# audio.net
KiCad netlist of a schematic drawn in Altium Designer
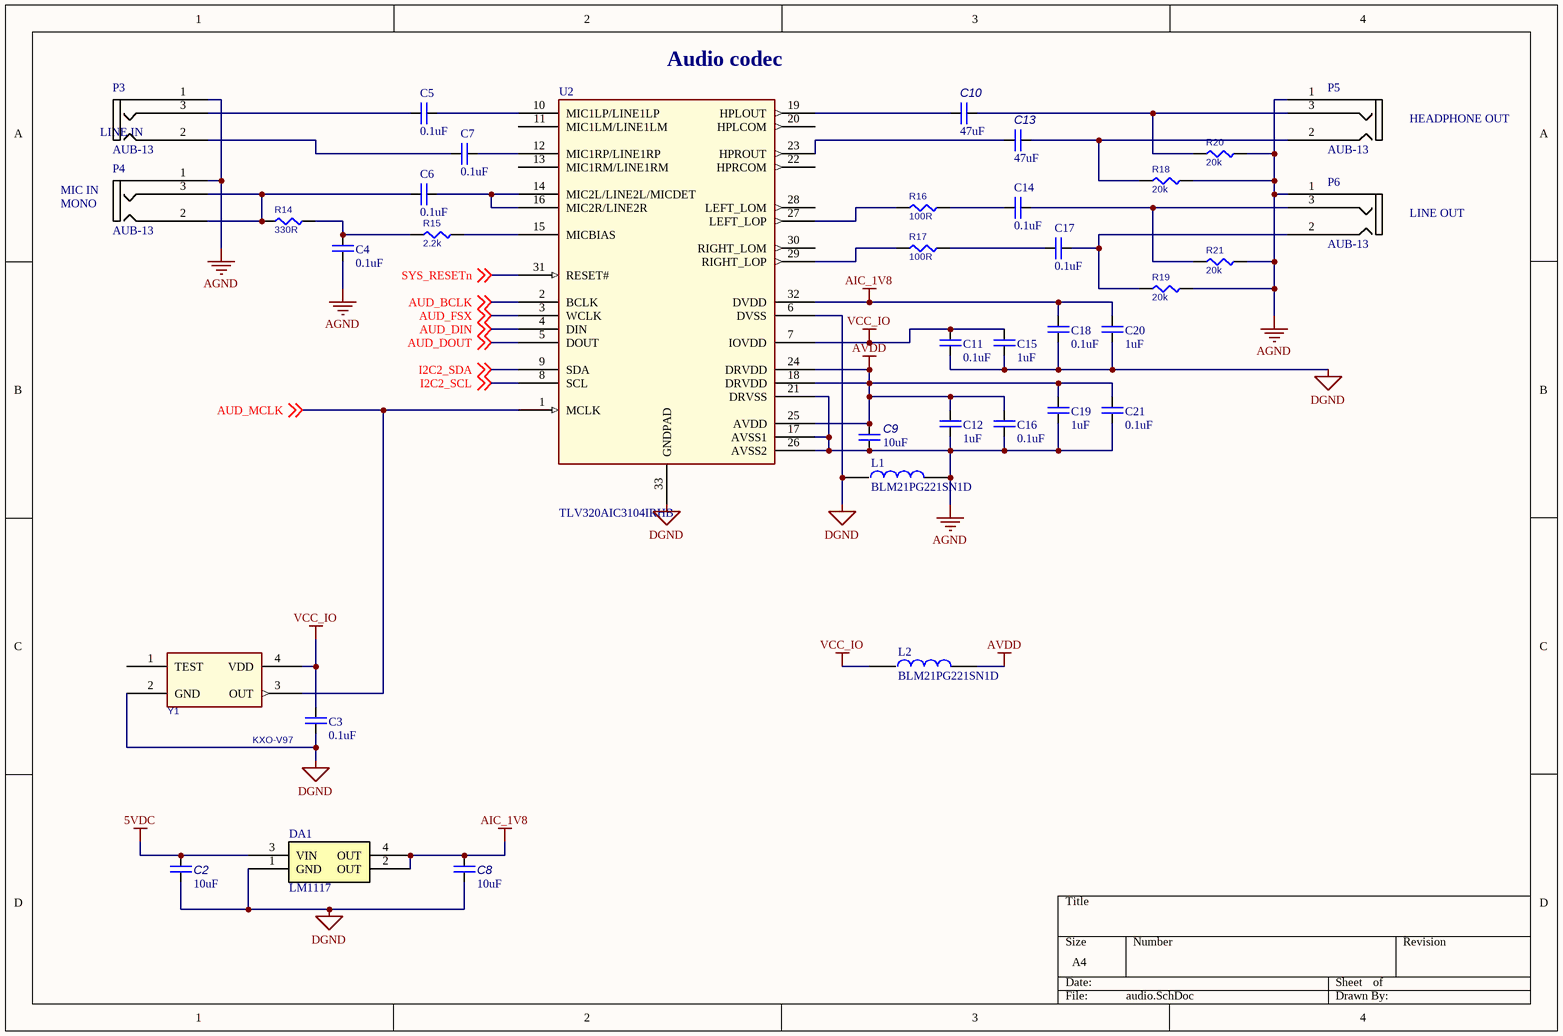
[diagram p0: audio.SchDoc]

(export (version "E")
  (design (tool "Eeschema 10.0.6"))
  (components
    (comp (ref "C2")
      (value "10uF")
      (footprint "CC2012-0805")
      (description "C0805")
      (libsource (lib "usomiq-audio") (part "C0805"))
    )
    (comp (ref "C3")
      (value "0.1uF")
      (footprint "CHIP0603")
      (description "Ceramic capacitor C0603")
      (fields (field (name "Comment") "C0603"))
      (libsource (lib "usomiq-audio") (part "C0603"))
    )
    (comp (ref "C4")
      (value "0.1uF")
      (footprint "CHIP0603")
      (description "Ceramic capacitor C0603")
      (fields (field (name "Comment") "C0603"))
      (libsource (lib "usomiq-audio") (part "C0603"))
    )
    (comp (ref "C5")
      (value "0.1uF")
      (footprint "CHIP0603")
      (description "Ceramic capacitor C0603")
      (fields (field (name "Comment") "C0603"))
      (libsource (lib "usomiq-audio") (part "C0603"))
    )
    (comp (ref "C6")
      (value "0.1uF")
      (footprint "CHIP0603")
      (description "Ceramic capacitor C0603")
      (fields (field (name "Comment") "C0603"))
      (libsource (lib "usomiq-audio") (part "C0603"))
    )
    (comp (ref "C7")
      (value "0.1uF")
      (footprint "CHIP0603")
      (description "Ceramic capacitor C0603")
      (fields (field (name "Comment") "C0603"))
      (libsource (lib "usomiq-audio") (part "C0603"))
    )
    (comp (ref "C8")
      (value "10uF")
      (footprint "CC2012-0805")
      (description "C0805")
      (libsource (lib "usomiq-audio") (part "C0805"))
    )
    (comp (ref "C9")
      (value "10uF")
      (footprint "CC2012-0805")
      (description "C0805")
      (libsource (lib "usomiq-audio") (part "C0805"))
    )
    (comp (ref "C10")
      (value "47uF")
      (footprint "CC3216-1206")
      (description "C1206")
      (libsource (lib "usomiq-audio") (part "C1206"))
    )
    (comp (ref "C11")
      (value "0.1uF")
      (footprint "CHIP0603")
      (description "Ceramic capacitor C0603")
      (fields (field (name "Comment") "C0603"))
      (libsource (lib "usomiq-audio") (part "C0603"))
    )
    (comp (ref "C12")
      (value "1uF")
      (footprint "CHIP0603")
      (description "Ceramic capacitor C0603")
      (fields (field (name "Comment") "C0603"))
      (libsource (lib "usomiq-audio") (part "C0603"))
    )
    (comp (ref "C13")
      (value "47uF")
      (footprint "CC3216-1206")
      (description "C1206")
      (libsource (lib "usomiq-audio") (part "C1206"))
    )
    (comp (ref "C14")
      (value "0.1uF")
      (footprint "CHIP0603")
      (description "Ceramic capacitor C0603")
      (fields (field (name "Comment") "C0603"))
      (libsource (lib "usomiq-audio") (part "C0603"))
    )
    (comp (ref "C15")
      (value "1uF")
      (footprint "CHIP0603")
      (description "Ceramic capacitor C0603")
      (fields (field (name "Comment") "C0603"))
      (libsource (lib "usomiq-audio") (part "C0603"))
    )
    (comp (ref "C16")
      (value "0.1uF")
      (footprint "CHIP0603")
      (description "Ceramic capacitor C0603")
      (fields (field (name "Comment") "C0603"))
      (libsource (lib "usomiq-audio") (part "C0603"))
    )
    (comp (ref "C17")
      (value "0.1uF")
      (footprint "CHIP0603")
      (description "Ceramic capacitor C0603")
      (fields (field (name "Comment") "C0603"))
      (libsource (lib "usomiq-audio") (part "C0603"))
    )
    (comp (ref "C18")
      (value "0.1uF")
      (footprint "CHIP0603")
      (description "Ceramic capacitor C0603")
      (fields (field (name "Comment") "C0603"))
      (libsource (lib "usomiq-audio") (part "C0603"))
    )
    (comp (ref "C19")
      (value "1uF")
      (footprint "CHIP0603")
      (description "Ceramic capacitor C0603")
      (fields (field (name "Comment") "C0603"))
      (libsource (lib "usomiq-audio") (part "C0603"))
    )
    (comp (ref "C20")
      (value "1uF")
      (footprint "CHIP0603")
      (description "Ceramic capacitor C0603")
      (fields (field (name "Comment") "C0603"))
      (libsource (lib "usomiq-audio") (part "C0603"))
    )
    (comp (ref "C21")
      (value "0.1uF")
      (footprint "CHIP0603")
      (description "Ceramic capacitor C0603")
      (fields (field (name "Comment") "C0603"))
      (libsource (lib "usomiq-audio") (part "C0603"))
    )
    (comp (ref "DA1")
      (value "LM1117")
      (footprint "SOT230P700X160-4N")
      (description "800mA Low-Dropout Linear Regulator")
      (fields (field (name "MANUFACTURER") "National"))
      (libsource (lib "usomiq-audio") (part "LM1117"))
    )
    (comp (ref "L1")
      (value "BLM21PG221SN1D")
      (footprint "Chip2PinSM127P600-8N")
      (fields (field (name "MANUFACTURER") "Murata"))
      (libsource (lib "usomiq-audio") (part "BLM21PG221SN1D"))
    )
    (comp (ref "L2")
      (value "BLM21PG221SN1D")
      (footprint "Chip2PinSM127P600-8N")
      (fields (field (name "MANUFACTURER") "Murata"))
      (libsource (lib "usomiq-audio") (part "BLM21PG221SN1D"))
    )
    (comp (ref "P3")
      (value "AUB-13")
      (footprint "AUB_13")
      (description "Audio connector mini-jack 3.5mm, 3 pins")
      (libsource (lib "usomiq-audio") (part "AUB-13"))
    )
    (comp (ref "P4")
      (value "AUB-13")
      (footprint "AUB_13")
      (description "Audio connector mini-jack 3.5mm, 3 pins")
      (libsource (lib "usomiq-audio") (part "AUB-13"))
    )
    (comp (ref "P5")
      (value "AUB-13")
      (footprint "AUB_13")
      (description "Audio connector mini-jack 3.5mm, 3 pins")
      (libsource (lib "usomiq-audio") (part "AUB-13"))
    )
    (comp (ref "P6")
      (value "AUB-13")
      (footprint "AUB_13")
      (description "Audio connector mini-jack 3.5mm, 3 pins")
      (libsource (lib "usomiq-audio") (part "AUB-13"))
    )
    (comp (ref "R14")
      (value "330R")
      (footprint "CHIP0603")
      (description "Resistor 0603")
      (fields (field (name "Comment") "R0603"))
      (libsource (lib "usomiq-audio") (part "R0603"))
    )
    (comp (ref "R15")
      (value "2.2k")
      (footprint "CHIP0603")
      (description "Resistor 0603")
      (fields (field (name "Comment") "R0603"))
      (libsource (lib "usomiq-audio") (part "R0603"))
    )
    (comp (ref "R16")
      (value "100R")
      (footprint "CHIP0603")
      (description "Resistor 0603")
      (fields (field (name "Comment") "R0603"))
      (libsource (lib "usomiq-audio") (part "R0603"))
    )
    (comp (ref "R17")
      (value "100R")
      (footprint "CHIP0603")
      (description "Resistor 0603")
      (fields (field (name "Comment") "R0603"))
      (libsource (lib "usomiq-audio") (part "R0603"))
    )
    (comp (ref "R18")
      (value "20k")
      (footprint "CHIP0603")
      (description "Resistor 0603")
      (fields (field (name "Comment") "R0603"))
      (libsource (lib "usomiq-audio") (part "R0603"))
    )
    (comp (ref "R19")
      (value "20k")
      (footprint "CHIP0603")
      (description "Resistor 0603")
      (fields (field (name "Comment") "R0603"))
      (libsource (lib "usomiq-audio") (part "R0603"))
    )
    (comp (ref "R20")
      (value "20k")
      (footprint "CHIP0603")
      (description "Resistor 0603")
      (fields (field (name "Comment") "R0603"))
      (libsource (lib "usomiq-audio") (part "R0603"))
    )
    (comp (ref "R21")
      (value "20k")
      (footprint "CHIP0603")
      (description "Resistor 0603")
      (fields (field (name "Comment") "R0603"))
      (libsource (lib "usomiq-audio") (part "R0603"))
    )
    (comp (ref "U2")
      (value "TLV320AIC3104")
      (footprint "QFN32")
      (description "LOW-POWER STEREO AUDIO CODEC FOR PORTABLE AUDIO/TELEPHONY")
      (fields (field (name "MANUFACTURER") "TI") (field (name "MAN P/N") "TLV320AIC3104IRHB"))
      (libsource (lib "usomiq-audio") (part "TLV320AIC3104"))
    )
    (comp (ref "Y1")
      (value "KXO-V97")
      (footprint "KXO_V97")
      (description "Quartz oscillator 7x5mm")
      (fields (field (name "MANUFACTURER") "Geyer"))
      (libsource (lib "usomiq-audio") (part "KXO-V97"))
    )
  )
  (nets
    (net (code "1") (name "5VDC") (class "Default")
      (node (ref "C2") (pin "2") (pinfunction "2_2") (pintype "passive"))
      (node (ref "DA1") (pin "3") (pinfunction "VIN_3") (pintype "power_in"))
    )
    (net (code "2") (name "AGND") (class "Default")
      (node (ref "C12") (pin "2") (pinfunction "2_2") (pintype "passive"))
      (node (ref "C16") (pin "2") (pinfunction "2_2") (pintype "passive"))
      (node (ref "C19") (pin "2") (pinfunction "2_2") (pintype "passive"))
      (node (ref "C21") (pin "2") (pinfunction "2_2") (pintype "passive"))
      (node (ref "C4") (pin "1") (pinfunction "1_1") (pintype "passive"))
      (node (ref "C9") (pin "1") (pinfunction "1_1") (pintype "passive"))
      (node (ref "L1") (pin "2") (pinfunction "2_2") (pintype "passive"))
      (node (ref "P3") (pin "1") (pinfunction "GND_1") (pintype "passive"))
      (node (ref "P4") (pin "1") (pinfunction "GND_1") (pintype "passive"))
      (node (ref "P5") (pin "1") (pinfunction "GND_1") (pintype "passive"))
      (node (ref "P6") (pin "1") (pinfunction "GND_1") (pintype "passive"))
      (node (ref "R18") (pin "1") (pinfunction "1_1") (pintype "passive"))
      (node (ref "R19") (pin "1") (pinfunction "1_1") (pintype "passive"))
      (node (ref "R20") (pin "1") (pinfunction "1_1") (pintype "passive"))
      (node (ref "R21") (pin "1") (pinfunction "1_1") (pintype "passive"))
      (node (ref "U2") (pin "17") (pinfunction "AVSS1_17") (pintype "power_in"))
      (node (ref "U2") (pin "21") (pinfunction "DRVSS_21") (pintype "power_in"))
      (node (ref "U2") (pin "26") (pinfunction "AVSS2_26") (pintype "power_in"))
    )
    (net (code "3") (name "AIC_1V8") (class "Default")
      (node (ref "C18") (pin "1") (pinfunction "1_1") (pintype "passive"))
      (node (ref "C20") (pin "1") (pinfunction "1_1") (pintype "passive"))
      (node (ref "C8") (pin "2") (pinfunction "2_2") (pintype "passive"))
      (node (ref "DA1") (pin "2") (pinfunction "OUT_2") (pintype "power_in"))
      (node (ref "DA1") (pin "4") (pinfunction "OUT_4") (pintype "power_in"))
      (node (ref "U2") (pin "32") (pinfunction "DVDD_32") (pintype "power_in"))
    )
    (net (code "4") (name "AUD_BCLK") (class "Default")
      (node (ref "U2") (pin "2") (pinfunction "BCLK_2") (pintype "passive"))
    )
    (net (code "5") (name "AUD_DIN") (class "Default")
      (node (ref "U2") (pin "4") (pinfunction "DIN_4") (pintype "passive"))
    )
    (net (code "6") (name "AUD_DOUT") (class "Default")
      (node (ref "U2") (pin "5") (pinfunction "DOUT_5") (pintype "passive"))
    )
    (net (code "7") (name "AUD_FSX") (class "Default")
      (node (ref "U2") (pin "3") (pinfunction "WCLK_3") (pintype "passive"))
    )
    (net (code "8") (name "AUD_MCLK") (class "Default")
      (node (ref "U2") (pin "1") (pinfunction "MCLK_1") (pintype "input"))
      (node (ref "Y1") (pin "3") (pinfunction "OUT_3") (pintype "output"))
    )
    (net (code "9") (name "AVDD") (class "Default")
      (node (ref "C12") (pin "1") (pinfunction "1_1") (pintype "passive"))
      (node (ref "C16") (pin "1") (pinfunction "1_1") (pintype "passive"))
      (node (ref "C19") (pin "1") (pinfunction "1_1") (pintype "passive"))
      (node (ref "C21") (pin "1") (pinfunction "1_1") (pintype "passive"))
      (node (ref "C9") (pin "2") (pinfunction "2_2") (pintype "passive"))
      (node (ref "L2") (pin "2") (pinfunction "2_2") (pintype "passive"))
      (node (ref "U2") (pin "18") (pinfunction "DRVDD_18") (pintype "power_in"))
      (node (ref "U2") (pin "24") (pinfunction "DRVDD_24") (pintype "power_in"))
      (node (ref "U2") (pin "25") (pinfunction "AVDD_25") (pintype "power_in"))
    )
    (net (code "10") (name "DGND") (class "Default")
      (node (ref "C11") (pin "2") (pinfunction "2_2") (pintype "passive"))
      (node (ref "C15") (pin "2") (pinfunction "2_2") (pintype "passive"))
      (node (ref "C18") (pin "2") (pinfunction "2_2") (pintype "passive"))
      (node (ref "C2") (pin "1") (pinfunction "1_1") (pintype "passive"))
      (node (ref "C20") (pin "2") (pinfunction "2_2") (pintype "passive"))
      (node (ref "C3") (pin "2") (pinfunction "2_2") (pintype "passive"))
      (node (ref "C8") (pin "1") (pinfunction "1_1") (pintype "passive"))
      (node (ref "DA1") (pin "1") (pinfunction "GND_1") (pintype "power_in"))
      (node (ref "L1") (pin "1") (pinfunction "1_1") (pintype "passive"))
      (node (ref "U2") (pin "33") (pinfunction "GNDPAD_33") (pintype "power_in"))
      (node (ref "U2") (pin "6") (pinfunction "DVSS_6") (pintype "power_in"))
      (node (ref "Y1") (pin "2") (pinfunction "GND_2") (pintype "power_in"))
    )
    (net (code "11") (name "I2C2_SCL") (class "Default")
      (node (ref "U2") (pin "8") (pinfunction "SCL_8") (pintype "passive"))
    )
    (net (code "12") (name "I2C2_SDA") (class "Default")
      (node (ref "U2") (pin "9") (pinfunction "SDA_9") (pintype "passive"))
    )
    (net (code "13") (name "Net-(C4-Pad2)") (class "Default")
      (node (ref "C4") (pin "2") (pinfunction "2_2") (pintype "passive"))
      (node (ref "R14") (pin "2") (pinfunction "2_2") (pintype "passive"))
      (node (ref "R15") (pin "1") (pinfunction "1_1") (pintype "passive"))
    )
    (net (code "14") (name "Net-(C14-Pad1)") (class "Default")
      (node (ref "C14") (pin "1") (pinfunction "1_1") (pintype "passive"))
      (node (ref "R16") (pin "2") (pinfunction "2_2") (pintype "passive"))
    )
    (net (code "15") (name "Net-(C17-Pad1)") (class "Default")
      (node (ref "C17") (pin "1") (pinfunction "1_1") (pintype "passive"))
      (node (ref "R17") (pin "2") (pinfunction "2_2") (pintype "passive"))
    )
    (net (code "16") (name "Net-(P3-LEFT)") (class "Default")
      (node (ref "C5") (pin "1") (pinfunction "1_1") (pintype "passive"))
      (node (ref "P3") (pin "3") (pinfunction "LEFT_3") (pintype "passive"))
    )
    (net (code "17") (name "Net-(P3-RIGHT)") (class "Default")
      (node (ref "C7") (pin "1") (pinfunction "1_1") (pintype "passive"))
      (node (ref "P3") (pin "2") (pinfunction "RIGHT_2") (pintype "passive"))
    )
    (net (code "18") (name "Net-(P4-LEFT)") (class "Default")
      (node (ref "C6") (pin "1") (pinfunction "1_1") (pintype "passive"))
      (node (ref "P4") (pin "2") (pinfunction "RIGHT_2") (pintype "passive"))
      (node (ref "P4") (pin "3") (pinfunction "LEFT_3") (pintype "passive"))
      (node (ref "R14") (pin "1") (pinfunction "1_1") (pintype "passive"))
    )
    (net (code "19") (name "Net-(P5-LEFT)") (class "Default")
      (node (ref "C10") (pin "1") (pinfunction "1_1") (pintype "passive"))
      (node (ref "P5") (pin "3") (pinfunction "LEFT_3") (pintype "passive"))
      (node (ref "R20") (pin "2") (pinfunction "2_2") (pintype "passive"))
    )
    (net (code "20") (name "Net-(P5-RIGHT)") (class "Default")
      (node (ref "C13") (pin "1") (pinfunction "1_1") (pintype "passive"))
      (node (ref "P5") (pin "2") (pinfunction "RIGHT_2") (pintype "passive"))
      (node (ref "R18") (pin "2") (pinfunction "2_2") (pintype "passive"))
    )
    (net (code "21") (name "Net-(P6-LEFT)") (class "Default")
      (node (ref "C14") (pin "2") (pinfunction "2_2") (pintype "passive"))
      (node (ref "P6") (pin "3") (pinfunction "LEFT_3") (pintype "passive"))
      (node (ref "R21") (pin "2") (pinfunction "2_2") (pintype "passive"))
    )
    (net (code "22") (name "Net-(P6-RIGHT)") (class "Default")
      (node (ref "C17") (pin "2") (pinfunction "2_2") (pintype "passive"))
      (node (ref "P6") (pin "2") (pinfunction "RIGHT_2") (pintype "passive"))
      (node (ref "R19") (pin "2") (pinfunction "2_2") (pintype "passive"))
    )
    (net (code "23") (name "Net-(U2-HPLOUT)") (class "Default")
      (node (ref "C10") (pin "2") (pinfunction "2_2") (pintype "passive"))
      (node (ref "U2") (pin "19") (pinfunction "HPLOUT_19") (pintype "output"))
    )
    (net (code "24") (name "Net-(U2-HPROUT)") (class "Default")
      (node (ref "C13") (pin "2") (pinfunction "2_2") (pintype "passive"))
      (node (ref "U2") (pin "23") (pinfunction "HPROUT_23") (pintype "output"))
    )
    (net (code "25") (name "Net-(U2-LEFT_LOP)") (class "Default")
      (node (ref "R16") (pin "1") (pinfunction "1_1") (pintype "passive"))
      (node (ref "U2") (pin "27") (pinfunction "LEFT_LOP_27") (pintype "output"))
    )
    (net (code "26") (name "Net-(U2-MIC1LP{slash}LINE1LP)") (class "Default")
      (node (ref "C5") (pin "2") (pinfunction "2_2") (pintype "passive"))
      (node (ref "U2") (pin "10") (pinfunction "MIC1LP/LINE1LP_10") (pintype "passive"))
    )
    (net (code "27") (name "Net-(U2-MIC1RP{slash}LINE1RP)") (class "Default")
      (node (ref "C7") (pin "2") (pinfunction "2_2") (pintype "passive"))
      (node (ref "U2") (pin "12") (pinfunction "MIC1RP/LINE1RP_12") (pintype "passive"))
    )
    (net (code "28") (name "Net-(U2-MIC2L{slash}LINE2L{slash}MICDET)") (class "Default")
      (node (ref "C6") (pin "2") (pinfunction "2_2") (pintype "passive"))
      (node (ref "U2") (pin "14") (pinfunction "MIC2L/LINE2L/MICDET_14") (pintype "passive"))
      (node (ref "U2") (pin "16") (pinfunction "MIC2R/LINE2R_16") (pintype "passive"))
    )
    (net (code "29") (name "Net-(U2-MICBIAS)") (class "Default")
      (node (ref "R15") (pin "2") (pinfunction "2_2") (pintype "passive"))
      (node (ref "U2") (pin "15") (pinfunction "MICBIAS_15") (pintype "passive"))
    )
    (net (code "30") (name "Net-(U2-RIGHT_LOP)") (class "Default")
      (node (ref "R17") (pin "1") (pinfunction "1_1") (pintype "passive"))
      (node (ref "U2") (pin "29") (pinfunction "RIGHT_LOP_29") (pintype "output"))
    )
    (net (code "31") (name "SYS_RESETn") (class "Default")
      (node (ref "U2") (pin "31") (pinfunction "RESET#_31") (pintype "input"))
    )
    (net (code "32") (name "VCC_IO") (class "Default")
      (node (ref "C11") (pin "1") (pinfunction "1_1") (pintype "passive"))
      (node (ref "C15") (pin "1") (pinfunction "1_1") (pintype "passive"))
      (node (ref "C3") (pin "1") (pinfunction "1_1") (pintype "passive"))
      (node (ref "L2") (pin "1") (pinfunction "1_1") (pintype "passive"))
      (node (ref "U2") (pin "7") (pinfunction "IOVDD_7") (pintype "power_in"))
      (node (ref "Y1") (pin "4") (pinfunction "VDD_4") (pintype "power_in"))
    )
    (net (code "33") (name "unconnected-(U2-HPLCOM-Pad20)") (class "Default")
      (node (ref "U2") (pin "20") (pinfunction "HPLCOM_20") (pintype "output"))
    )
    (net (code "34") (name "unconnected-(U2-HPRCOM-Pad22)") (class "Default")
      (node (ref "U2") (pin "22") (pinfunction "HPRCOM_22") (pintype "output"))
    )
    (net (code "35") (name "unconnected-(U2-LEFT_LOM-Pad28)") (class "Default")
      (node (ref "U2") (pin "28") (pinfunction "LEFT_LOM_28") (pintype "output"))
    )
    (net (code "36") (name "unconnected-(U2-MIC1LM{slash}LINE1LM-Pad11)") (class "Default")
      (node (ref "U2") (pin "11") (pinfunction "MIC1LM/LINE1LM_11") (pintype "passive"))
    )
    (net (code "37") (name "unconnected-(U2-MIC1RM{slash}LINE1RM-Pad13)") (class "Default")
      (node (ref "U2") (pin "13") (pinfunction "MIC1RM/LINE1RM_13") (pintype "passive"))
    )
    (net (code "38") (name "unconnected-(U2-RIGHT_LOM-Pad30)") (class "Default")
      (node (ref "U2") (pin "30") (pinfunction "RIGHT_LOM_30") (pintype "output"))
    )
    (net (code "39") (name "unconnected-(Y1-TEST-Pad1)") (class "Default")
      (node (ref "Y1") (pin "1") (pinfunction "TEST_1") (pintype "passive"))
    )
  )
)
